# sch1.net
KiCad netlist of a schematic drawn in EAGLE
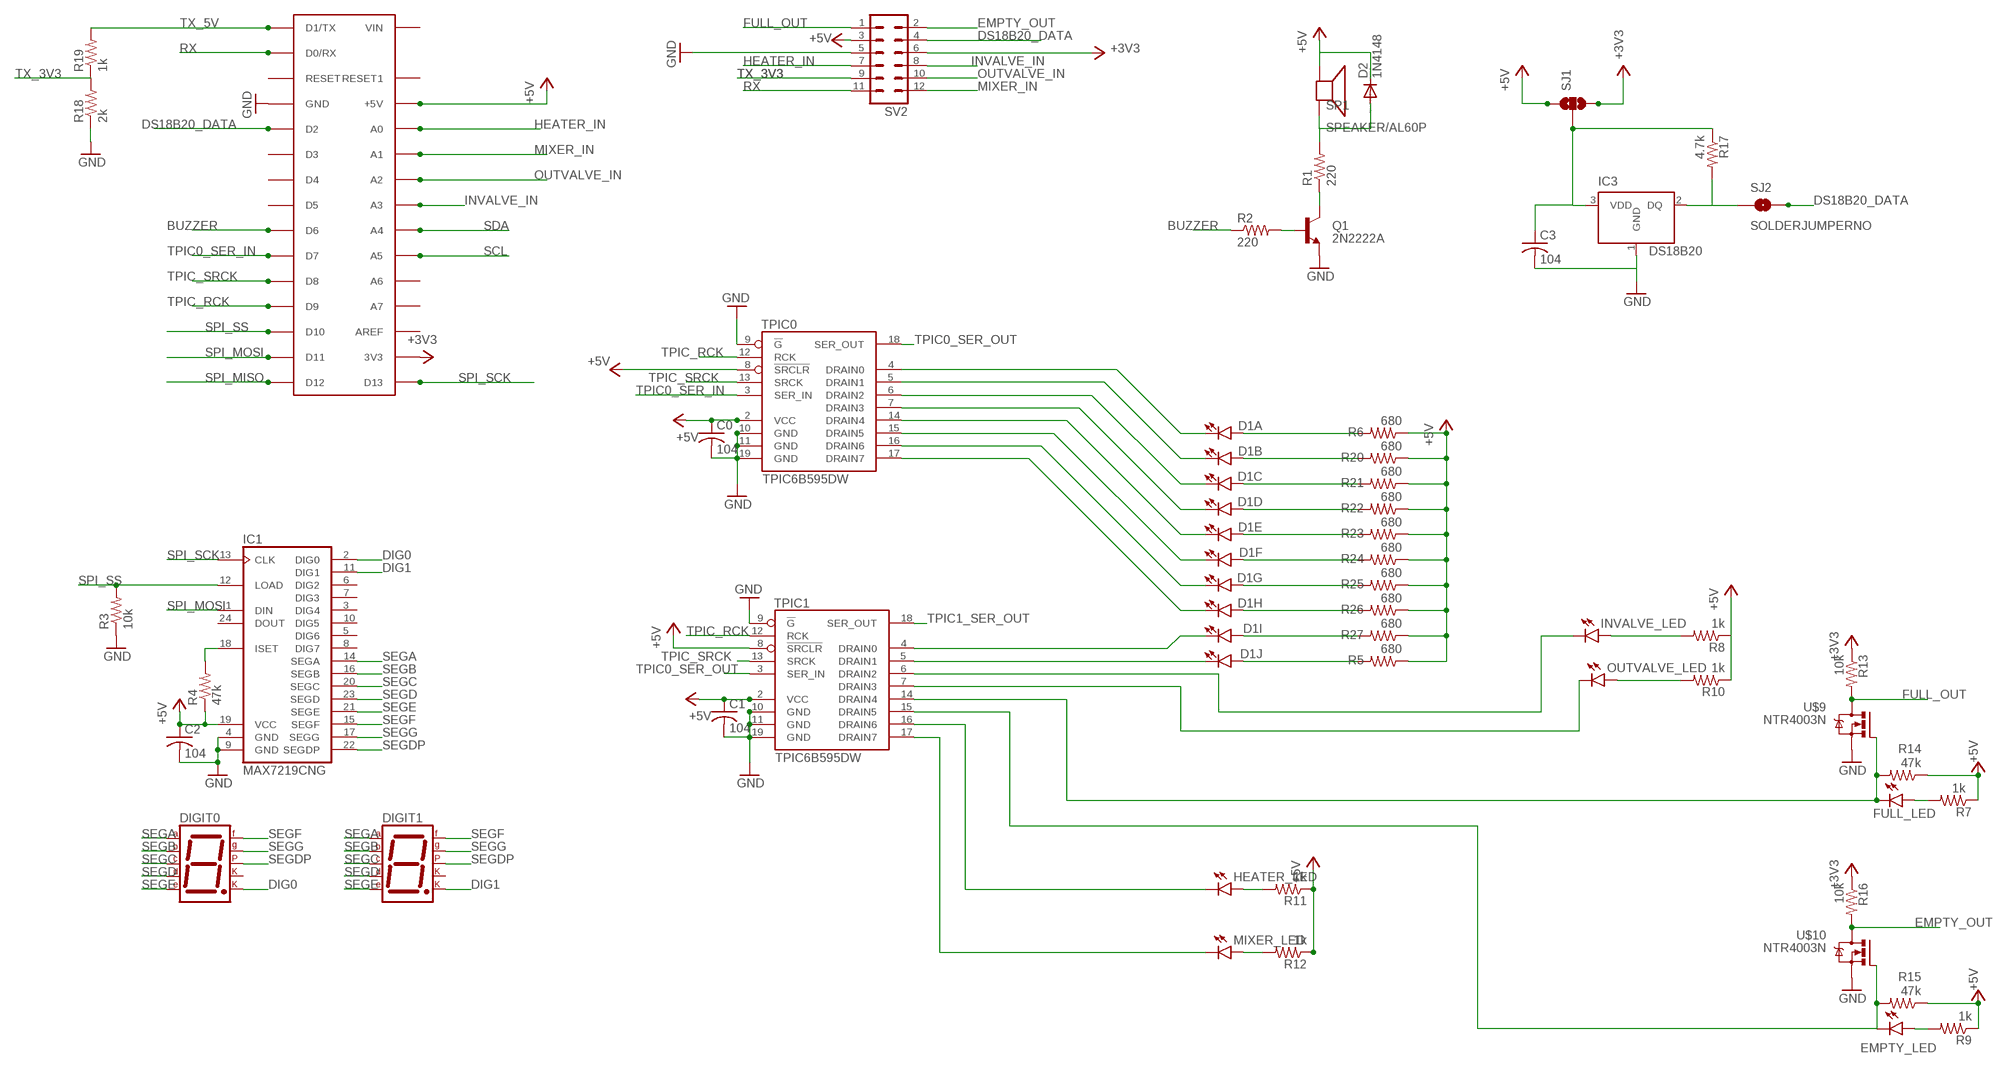
[diagram p0: schematic, sheet 1]

(export (version "E")
  (design (tool "Eeschema 10.0.6"))
  (components
    (comp (ref "ARDUINO")
      (value "ARDUINONANO")
      (footprint "eagle-import:PDIP-32")
      (libsource (lib "eagle-import") (part "ARDUINONANO"))
    )
    (comp (ref "C0")
      (value "104")
      (footprint "eagle-import:C0603")
      (libsource (lib "eagle-import") (part "C-USC0603"))
    )
    (comp (ref "C1")
      (value "104")
      (footprint "eagle-import:C0603")
      (libsource (lib "eagle-import") (part "C-USC0603"))
    )
    (comp (ref "C2")
      (value "104")
      (footprint "eagle-import:C0603")
      (libsource (lib "eagle-import") (part "C-USC0603"))
    )
    (comp (ref "C3")
      (value "104")
      (footprint "eagle-import:C0603")
      (libsource (lib "eagle-import") (part "C-USC0603"))
    )
    (comp (ref "D1")
      (value "LED_BARGRAPH_10")
      (footprint "eagle-import:LED_BARGAPH_10")
      (libsource (lib "eagle-import") (part "LED_BARGRAPH_10"))
    )
    (comp (ref "D2")
      (value "1N4148")
      (footprint "eagle-import:DO35-7")
      (libsource (lib "eagle-import") (part "1N4148DO35-7"))
    )
    (comp (ref "DIGIT0")
      (value "7SEG-CK")
      (footprint "eagle-import:7SEG-13")
      (libsource (lib "eagle-import") (part "7SEG-CK"))
    )
    (comp (ref "DIGIT1")
      (value "7SEG-CK")
      (footprint "eagle-import:7SEG-13")
      (libsource (lib "eagle-import") (part "7SEG-CK"))
    )
    (comp (ref "EMPTY_LED")
      (value "LED0603")
      (footprint "eagle-import:LED-0603")
      (libsource (lib "eagle-import") (part "LED0603"))
    )
    (comp (ref "FULL_LED")
      (value "LED0603")
      (footprint "eagle-import:LED-0603")
      (libsource (lib "eagle-import") (part "LED0603"))
    )
    (comp (ref "HEATER_LED")
      (value "LED0603")
      (footprint "eagle-import:LED-0603")
      (libsource (lib "eagle-import") (part "LED0603"))
    )
    (comp (ref "IC1")
      (value "MAX7219CNG")
      (footprint "eagle-import:DIL24-3")
      (fields (field (name "MF") "MAXIM"))
      (libsource (lib "eagle-import") (part "MAX7219CNG"))
    )
    (comp (ref "IC3")
      (value "DS18B20")
      (footprint "eagle-import:TO-92")
      (libsource (lib "eagle-import") (part "DS18B20"))
    )
    (comp (ref "INVALVE_LED")
      (value "LED0603")
      (footprint "eagle-import:LED-0603")
      (libsource (lib "eagle-import") (part "LED0603"))
    )
    (comp (ref "MIXER_LED")
      (value "LED0603")
      (footprint "eagle-import:LED-0603")
      (libsource (lib "eagle-import") (part "LED0603"))
    )
    (comp (ref "OUTVALVE_LED")
      (value "LED0603")
      (footprint "eagle-import:LED-0603")
      (libsource (lib "eagle-import") (part "LED0603"))
    )
    (comp (ref "Q1")
      (value "2N2222A")
      (footprint "eagle-import:SOT23-3")
      (libsource (lib "eagle-import") (part "TRANSISTOR_NPNMMBT2222A"))
    )
    (comp (ref "R1")
      (value "220")
      (footprint "eagle-import:R0603")
      (libsource (lib "eagle-import") (part "R-US_R0603"))
    )
    (comp (ref "R2")
      (value "220")
      (footprint "eagle-import:R0603")
      (libsource (lib "eagle-import") (part "R-US_R0603"))
    )
    (comp (ref "R3")
      (value "10k")
      (footprint "eagle-import:R0603")
      (libsource (lib "eagle-import") (part "R-US_R0603"))
    )
    (comp (ref "R4")
      (value "47k")
      (footprint "eagle-import:R0603")
      (libsource (lib "eagle-import") (part "R-US_R0603"))
    )
    (comp (ref "R5")
      (value "680")
      (footprint "eagle-import:R0603")
      (libsource (lib "eagle-import") (part "R-US_R0603"))
    )
    (comp (ref "R6")
      (value "680")
      (footprint "eagle-import:R0603")
      (libsource (lib "eagle-import") (part "R-US_R0603"))
    )
    (comp (ref "R7")
      (value "1k")
      (footprint "eagle-import:R0603")
      (libsource (lib "eagle-import") (part "R-US_R0603"))
    )
    (comp (ref "R8")
      (value "1k")
      (footprint "eagle-import:R0603")
      (libsource (lib "eagle-import") (part "R-US_R0603"))
    )
    (comp (ref "R9")
      (value "1k")
      (footprint "eagle-import:R0603")
      (libsource (lib "eagle-import") (part "R-US_R0603"))
    )
    (comp (ref "R10")
      (value "1k")
      (footprint "eagle-import:R0603")
      (libsource (lib "eagle-import") (part "R-US_R0603"))
    )
    (comp (ref "R11")
      (value "1k")
      (footprint "eagle-import:R0603")
      (libsource (lib "eagle-import") (part "R-US_R0603"))
    )
    (comp (ref "R12")
      (value "1k")
      (footprint "eagle-import:R0603")
      (libsource (lib "eagle-import") (part "R-US_R0603"))
    )
    (comp (ref "R13")
      (value "10k")
      (footprint "eagle-import:R0603")
      (libsource (lib "eagle-import") (part "R-US_R0603"))
    )
    (comp (ref "R14")
      (value "47k")
      (footprint "eagle-import:R0603")
      (libsource (lib "eagle-import") (part "R-US_R0603"))
    )
    (comp (ref "R15")
      (value "47k")
      (footprint "eagle-import:R0603")
      (libsource (lib "eagle-import") (part "R-US_R0603"))
    )
    (comp (ref "R16")
      (value "10k")
      (footprint "eagle-import:R0603")
      (libsource (lib "eagle-import") (part "R-US_R0603"))
    )
    (comp (ref "R17")
      (value "4.7k")
      (footprint "eagle-import:R0603")
      (libsource (lib "eagle-import") (part "R-US_R0603"))
    )
    (comp (ref "R18")
      (value "2k")
      (footprint "eagle-import:R0603")
      (libsource (lib "eagle-import") (part "R-US_R0603"))
    )
    (comp (ref "R19")
      (value "1k")
      (footprint "eagle-import:R0603")
      (libsource (lib "eagle-import") (part "R-US_R0603"))
    )
    (comp (ref "R20")
      (value "680")
      (footprint "eagle-import:R0603")
      (libsource (lib "eagle-import") (part "R-US_R0603"))
    )
    (comp (ref "R21")
      (value "680")
      (footprint "eagle-import:R0603")
      (libsource (lib "eagle-import") (part "R-US_R0603"))
    )
    (comp (ref "R22")
      (value "680")
      (footprint "eagle-import:R0603")
      (libsource (lib "eagle-import") (part "R-US_R0603"))
    )
    (comp (ref "R23")
      (value "680")
      (footprint "eagle-import:R0603")
      (libsource (lib "eagle-import") (part "R-US_R0603"))
    )
    (comp (ref "R24")
      (value "680")
      (footprint "eagle-import:R0603")
      (libsource (lib "eagle-import") (part "R-US_R0603"))
    )
    (comp (ref "R25")
      (value "680")
      (footprint "eagle-import:R0603")
      (libsource (lib "eagle-import") (part "R-US_R0603"))
    )
    (comp (ref "R26")
      (value "680")
      (footprint "eagle-import:R0603")
      (libsource (lib "eagle-import") (part "R-US_R0603"))
    )
    (comp (ref "R27")
      (value "680")
      (footprint "eagle-import:R0603")
      (libsource (lib "eagle-import") (part "R-US_R0603"))
    )
    (comp (ref "SJ1")
      (value "SOLDERJUMPER_2WAYS")
      (footprint "eagle-import:SJ_3")
      (libsource (lib "eagle-import") (part "SOLDERJUMPER_2WAYS"))
    )
    (comp (ref "SJ2")
      (value "SOLDERJUMPERNO")
      (footprint "eagle-import:SJ_2S-NO")
      (libsource (lib "eagle-import") (part "SOLDERJUMPERNO"))
    )
    (comp (ref "SP1")
      (value "SPEAKER/AL60P")
      (footprint "eagle-import:AL60P")
      (libsource (lib "eagle-import") (part "SPEAKER/AL60P"))
    )
    (comp (ref "SV2")
      (value "MA06-2")
      (footprint "eagle-import:MA06-2")
      (libsource (lib "eagle-import") (part "MA06-2"))
    )
    (comp (ref "TPIC0")
      (value "TPIC6B595DW")
      (footprint "eagle-import:SO20W")
      (libsource (lib "eagle-import") (part "TPIC6B595DW"))
    )
    (comp (ref "TPIC1")
      (value "TPIC6B595DW")
      (footprint "eagle-import:SO20W")
      (libsource (lib "eagle-import") (part "TPIC6B595DW"))
    )
    (comp (ref "U$9")
      (value "NTR4003N")
      (footprint "eagle-import:SOT23")
      (libsource (lib "eagle-import") (part "NTR4003N"))
    )
    (comp (ref "U$10")
      (value "NTR4003N")
      (footprint "eagle-import:SOT23")
      (libsource (lib "eagle-import") (part "NTR4003N"))
    )
  )
  (nets
    (net (code "1") (name "+3V3") (class "Default")
      (node (ref "ARDUINO") (pin "17") (pinfunction "3V3_17") (pintype "bidirectional"))
      (node (ref "R13") (pin "1") (pinfunction "1_1") (pintype "passive"))
      (node (ref "R16") (pin "1") (pinfunction "1_1") (pintype "passive"))
      (node (ref "SJ1") (pin "3") (pinfunction "3_3") (pintype "passive"))
      (node (ref "SV2") (pin "6") (pinfunction "6_6") (pintype "passive"))
    )
    (net (code "2") (name "+5V") (class "Default")
      (node (ref "ARDUINO") (pin "27") (pinfunction "+5V_27") (pintype "bidirectional"))
      (node (ref "C0") (pin "1") (pinfunction "1_1") (pintype "passive"))
      (node (ref "C1") (pin "1") (pinfunction "1_1") (pintype "passive"))
      (node (ref "C2") (pin "1") (pinfunction "1_1") (pintype "passive"))
      (node (ref "D2") (pin "C") (pinfunction "C_C") (pintype "passive"))
      (node (ref "IC1") (pin "19") (pinfunction "VCC_19") (pintype "power_in"))
      (node (ref "R10") (pin "1") (pinfunction "1_1") (pintype "passive"))
      (node (ref "R11") (pin "1") (pinfunction "1_1") (pintype "passive"))
      (node (ref "R12") (pin "1") (pinfunction "1_1") (pintype "passive"))
      (node (ref "R14") (pin "1") (pinfunction "1_1") (pintype "passive"))
      (node (ref "R15") (pin "1") (pinfunction "1_1") (pintype "passive"))
      (node (ref "R20") (pin "1") (pinfunction "1_1") (pintype "passive"))
      (node (ref "R21") (pin "1") (pinfunction "1_1") (pintype "passive"))
      (node (ref "R22") (pin "1") (pinfunction "1_1") (pintype "passive"))
      (node (ref "R23") (pin "1") (pinfunction "1_1") (pintype "passive"))
      (node (ref "R24") (pin "1") (pinfunction "1_1") (pintype "passive"))
      (node (ref "R25") (pin "1") (pinfunction "1_1") (pintype "passive"))
      (node (ref "R26") (pin "1") (pinfunction "1_1") (pintype "passive"))
      (node (ref "R27") (pin "1") (pinfunction "1_1") (pintype "passive"))
      (node (ref "R4") (pin "1") (pinfunction "1_1") (pintype "passive"))
      (node (ref "R5") (pin "1") (pinfunction "1_1") (pintype "passive"))
      (node (ref "R6") (pin "1") (pinfunction "1_1") (pintype "passive"))
      (node (ref "R7") (pin "1") (pinfunction "1_1") (pintype "passive"))
      (node (ref "R8") (pin "1") (pinfunction "1_1") (pintype "passive"))
      (node (ref "R9") (pin "1") (pinfunction "1_1") (pintype "passive"))
      (node (ref "SJ1") (pin "1") (pinfunction "1_1") (pintype "passive"))
      (node (ref "SP1") (pin "1") (pinfunction "+_1") (pintype "passive"))
      (node (ref "SV2") (pin "3") (pinfunction "3_3") (pintype "passive"))
      (node (ref "TPIC0") (pin "2") (pinfunction "VCC_2") (pintype "power_in"))
      (node (ref "TPIC0") (pin "8") (pinfunction "~{SRCLR}_8") (pintype "input"))
      (node (ref "TPIC1") (pin "2") (pinfunction "VCC_2") (pintype "power_in"))
      (node (ref "TPIC1") (pin "8") (pinfunction "~{SRCLR}_8") (pintype "input"))
    )
    (net (code "3") (name "/BUZZER") (class "Default")
      (node (ref "ARDUINO") (pin "9") (pinfunction "D6_9") (pintype "bidirectional"))
      (node (ref "R2") (pin "1") (pinfunction "1_1") (pintype "passive"))
    )
    (net (code "4") (name "/DIG0") (class "Default")
      (node (ref "DIGIT0") (pin "8") (pinfunction "CK2_8") (pintype "passive"))
      (node (ref "IC1") (pin "2") (pinfunction "DIG0_2") (pintype "output"))
    )
    (net (code "5") (name "/DIG1") (class "Default")
      (node (ref "DIGIT1") (pin "8") (pinfunction "CK2_8") (pintype "passive"))
      (node (ref "IC1") (pin "11") (pinfunction "DIG1_11") (pintype "output"))
    )
    (net (code "6") (name "/DS18B20_DATA") (class "Default")
      (node (ref "ARDUINO") (pin "5") (pinfunction "D2_5") (pintype "bidirectional"))
      (node (ref "SJ2") (pin "2") (pinfunction "2_2") (pintype "passive"))
      (node (ref "SV2") (pin "4") (pinfunction "4_4") (pintype "passive"))
    )
    (net (code "7") (name "/EMPTY_OUT") (class "Default")
      (node (ref "R16") (pin "2") (pinfunction "2_2") (pintype "passive"))
      (node (ref "SV2") (pin "2") (pinfunction "2_2") (pintype "passive"))
      (node (ref "U$10") (pin "3") (pinfunction "D_3") (pintype "passive"))
    )
    (net (code "8") (name "/FULL_OUT") (class "Default")
      (node (ref "R13") (pin "2") (pinfunction "2_2") (pintype "passive"))
      (node (ref "SV2") (pin "1") (pinfunction "1_1") (pintype "passive"))
      (node (ref "U$9") (pin "3") (pinfunction "D_3") (pintype "passive"))
    )
    (net (code "9") (name "/HEATER_IN") (class "Default")
      (node (ref "ARDUINO") (pin "19") (pinfunction "A0_19") (pintype "bidirectional"))
      (node (ref "SV2") (pin "7") (pinfunction "7_7") (pintype "passive"))
    )
    (net (code "10") (name "/INVALVE_IN") (class "Default")
      (node (ref "ARDUINO") (pin "22") (pinfunction "A3_22") (pintype "bidirectional"))
      (node (ref "SV2") (pin "8") (pinfunction "8_8") (pintype "passive"))
    )
    (net (code "11") (name "/MIXER_IN") (class "Default")
      (node (ref "ARDUINO") (pin "20") (pinfunction "A1_20") (pintype "bidirectional"))
      (node (ref "SV2") (pin "12") (pinfunction "12_12") (pintype "passive"))
    )
    (net (code "12") (name "/OUTVALVE_IN") (class "Default")
      (node (ref "ARDUINO") (pin "21") (pinfunction "A2_21") (pintype "bidirectional"))
      (node (ref "SV2") (pin "10") (pinfunction "10_10") (pintype "passive"))
    )
    (net (code "13") (name "/RX") (class "Default")
      (node (ref "ARDUINO") (pin "2") (pinfunction "D0/RX_2") (pintype "bidirectional"))
      (node (ref "SV2") (pin "11") (pinfunction "11_11") (pintype "passive"))
    )
    (net (code "14") (name "/SCL") (class "Default")
      (node (ref "ARDUINO") (pin "24") (pinfunction "A5_24") (pintype "bidirectional"))
    )
    (net (code "15") (name "/SDA") (class "Default")
      (node (ref "ARDUINO") (pin "23") (pinfunction "A4_23") (pintype "bidirectional"))
    )
    (net (code "16") (name "/SEGA") (class "Default")
      (node (ref "DIGIT0") (pin "7") (pinfunction "A_7") (pintype "passive"))
      (node (ref "DIGIT1") (pin "7") (pinfunction "A_7") (pintype "passive"))
      (node (ref "IC1") (pin "14") (pinfunction "SEGA_14") (pintype "output"))
    )
    (net (code "17") (name "/SEGB") (class "Default")
      (node (ref "DIGIT0") (pin "6") (pinfunction "B_6") (pintype "passive"))
      (node (ref "DIGIT1") (pin "6") (pinfunction "B_6") (pintype "passive"))
      (node (ref "IC1") (pin "16") (pinfunction "SEGB_16") (pintype "output"))
    )
    (net (code "18") (name "/SEGC") (class "Default")
      (node (ref "DIGIT0") (pin "4") (pinfunction "C_4") (pintype "passive"))
      (node (ref "DIGIT1") (pin "4") (pinfunction "C_4") (pintype "passive"))
      (node (ref "IC1") (pin "20") (pinfunction "SEGC_20") (pintype "output"))
    )
    (net (code "19") (name "/SEGD") (class "Default")
      (node (ref "DIGIT0") (pin "2") (pinfunction "D_2") (pintype "passive"))
      (node (ref "DIGIT1") (pin "2") (pinfunction "D_2") (pintype "passive"))
      (node (ref "IC1") (pin "23") (pinfunction "SEGD_23") (pintype "output"))
    )
    (net (code "20") (name "/SEGDP") (class "Default")
      (node (ref "DIGIT0") (pin "5") (pinfunction "DP_5") (pintype "passive"))
      (node (ref "DIGIT1") (pin "5") (pinfunction "DP_5") (pintype "passive"))
      (node (ref "IC1") (pin "22") (pinfunction "SEGDP_22") (pintype "output"))
    )
    (net (code "21") (name "/SEGE") (class "Default")
      (node (ref "DIGIT0") (pin "1") (pinfunction "E_1") (pintype "passive"))
      (node (ref "DIGIT1") (pin "1") (pinfunction "E_1") (pintype "passive"))
      (node (ref "IC1") (pin "21") (pinfunction "SEGE_21") (pintype "output"))
    )
    (net (code "22") (name "/SEGF") (class "Default")
      (node (ref "DIGIT0") (pin "9") (pinfunction "F_9") (pintype "passive"))
      (node (ref "DIGIT1") (pin "9") (pinfunction "F_9") (pintype "passive"))
      (node (ref "IC1") (pin "15") (pinfunction "SEGF_15") (pintype "output"))
    )
    (net (code "23") (name "/SEGG") (class "Default")
      (node (ref "DIGIT0") (pin "10") (pinfunction "G_10") (pintype "passive"))
      (node (ref "DIGIT1") (pin "10") (pinfunction "G_10") (pintype "passive"))
      (node (ref "IC1") (pin "17") (pinfunction "SEGG_17") (pintype "output"))
    )
    (net (code "24") (name "/SPI_MISO") (class "Default")
      (node (ref "ARDUINO") (pin "15") (pinfunction "D12_15") (pintype "bidirectional"))
    )
    (net (code "25") (name "/SPI_MOSI") (class "Default")
      (node (ref "ARDUINO") (pin "14") (pinfunction "D11_14") (pintype "bidirectional"))
      (node (ref "IC1") (pin "1") (pinfunction "DIN_1") (pintype "input"))
    )
    (net (code "26") (name "/SPI_SCK") (class "Default")
      (node (ref "ARDUINO") (pin "16") (pinfunction "D13_16") (pintype "bidirectional"))
      (node (ref "IC1") (pin "13") (pinfunction "CLK_13") (pintype "input"))
    )
    (net (code "27") (name "/SPI_SS") (class "Default")
      (node (ref "ARDUINO") (pin "13") (pinfunction "D10_13") (pintype "bidirectional"))
      (node (ref "IC1") (pin "12") (pinfunction "LOAD_12") (pintype "input"))
      (node (ref "R3") (pin "2") (pinfunction "2_2") (pintype "passive"))
    )
    (net (code "28") (name "/TPIC0_SER_IN") (class "Default")
      (node (ref "ARDUINO") (pin "10") (pinfunction "D7_10") (pintype "bidirectional"))
      (node (ref "TPIC0") (pin "3") (pinfunction "SER_IN_3") (pintype "input"))
    )
    (net (code "29") (name "/TPIC0_SER_OUT") (class "Default")
      (node (ref "TPIC0") (pin "18") (pinfunction "SER_OUT_18") (pintype "output"))
      (node (ref "TPIC1") (pin "3") (pinfunction "SER_IN_3") (pintype "input"))
    )
    (net (code "30") (name "/TPIC1_SER_OUT") (class "Default")
      (node (ref "TPIC1") (pin "18") (pinfunction "SER_OUT_18") (pintype "output"))
    )
    (net (code "31") (name "/TPIC_RCK") (class "Default")
      (node (ref "ARDUINO") (pin "12") (pinfunction "D9_12") (pintype "bidirectional"))
      (node (ref "TPIC0") (pin "12") (pinfunction "RCK_12") (pintype "input"))
      (node (ref "TPIC1") (pin "12") (pinfunction "RCK_12") (pintype "input"))
    )
    (net (code "32") (name "/TPIC_SRCK") (class "Default")
      (node (ref "ARDUINO") (pin "11") (pinfunction "D8_11") (pintype "bidirectional"))
      (node (ref "TPIC0") (pin "13") (pinfunction "SRCK_13") (pintype "input"))
      (node (ref "TPIC1") (pin "13") (pinfunction "SRCK_13") (pintype "input"))
    )
    (net (code "33") (name "/TX_3V3") (class "Default")
      (node (ref "R18") (pin "2") (pinfunction "2_2") (pintype "passive"))
      (node (ref "R19") (pin "1") (pinfunction "1_1") (pintype "passive"))
      (node (ref "SV2") (pin "9") (pinfunction "9_9") (pintype "passive"))
    )
    (net (code "34") (name "/TX_5V") (class "Default")
      (node (ref "ARDUINO") (pin "1") (pinfunction "D1/TX_1") (pintype "bidirectional"))
      (node (ref "R19") (pin "2") (pinfunction "2_2") (pintype "passive"))
    )
    (net (code "35") (name "GND") (class "Default")
      (node (ref "ARDUINO") (pin "29") (pinfunction "GND_29") (pintype "bidirectional"))
      (node (ref "ARDUINO") (pin "4") (pinfunction "GND_4") (pintype "bidirectional"))
      (node (ref "C0") (pin "2") (pinfunction "2_2") (pintype "passive"))
      (node (ref "C1") (pin "2") (pinfunction "2_2") (pintype "passive"))
      (node (ref "C2") (pin "2") (pinfunction "2_2") (pintype "passive"))
      (node (ref "C3") (pin "2") (pinfunction "2_2") (pintype "passive"))
      (node (ref "IC1") (pin "4") (pinfunction "GND_4") (pintype "power_in"))
      (node (ref "IC1") (pin "9") (pinfunction "GND_9") (pintype "power_in"))
      (node (ref "IC3") (pin "1") (pinfunction "GND_1") (pintype "power_in"))
      (node (ref "Q1") (pin "2") (pinfunction "E_2") (pintype "passive"))
      (node (ref "R18") (pin "1") (pinfunction "1_1") (pintype "passive"))
      (node (ref "R3") (pin "1") (pinfunction "1_1") (pintype "passive"))
      (node (ref "SV2") (pin "5") (pinfunction "5_5") (pintype "passive"))
      (node (ref "TPIC0") (pin "10") (pinfunction "GND_10") (pintype "power_in"))
      (node (ref "TPIC0") (pin "11") (pinfunction "GND_11") (pintype "power_in"))
      (node (ref "TPIC0") (pin "19") (pinfunction "GND_19") (pintype "power_in"))
      (node (ref "TPIC0") (pin "9") (pinfunction "~{G}_9") (pintype "input"))
      (node (ref "TPIC1") (pin "10") (pinfunction "GND_10") (pintype "power_in"))
      (node (ref "TPIC1") (pin "11") (pinfunction "GND_11") (pintype "power_in"))
      (node (ref "TPIC1") (pin "19") (pinfunction "GND_19") (pintype "power_in"))
      (node (ref "TPIC1") (pin "9") (pinfunction "~{G}_9") (pintype "input"))
      (node (ref "U$10") (pin "2") (pinfunction "S_2") (pintype "passive"))
      (node (ref "U$9") (pin "2") (pinfunction "S_2") (pintype "passive"))
    )
    (net (code "36") (name "Net-(D1A-A)") (class "Default")
      (node (ref "D1") (pin "1") (pinfunction "A_1") (pintype "passive"))
      (node (ref "R6") (pin "2") (pinfunction "2_2") (pintype "passive"))
    )
    (net (code "37") (name "Net-(D1A-C)") (class "Default")
      (node (ref "D1") (pin "20") (pinfunction "C_20") (pintype "passive"))
      (node (ref "TPIC0") (pin "4") (pinfunction "DRAIN0_4") (pintype "open_collector"))
    )
    (net (code "38") (name "Net-(D1B-A)") (class "Default")
      (node (ref "D1") (pin "2") (pinfunction "A_2") (pintype "passive"))
      (node (ref "R20") (pin "2") (pinfunction "2_2") (pintype "passive"))
    )
    (net (code "39") (name "Net-(D1B-C)") (class "Default")
      (node (ref "D1") (pin "19") (pinfunction "C_19") (pintype "passive"))
      (node (ref "TPIC0") (pin "5") (pinfunction "DRAIN1_5") (pintype "open_collector"))
    )
    (net (code "40") (name "Net-(D1C-A)") (class "Default")
      (node (ref "D1") (pin "3") (pinfunction "A_3") (pintype "passive"))
      (node (ref "R21") (pin "2") (pinfunction "2_2") (pintype "passive"))
    )
    (net (code "41") (name "Net-(D1C-C)") (class "Default")
      (node (ref "D1") (pin "18") (pinfunction "C_18") (pintype "passive"))
      (node (ref "TPIC0") (pin "6") (pinfunction "DRAIN2_6") (pintype "open_collector"))
    )
    (net (code "42") (name "Net-(D1D-A)") (class "Default")
      (node (ref "D1") (pin "4") (pinfunction "A_4") (pintype "passive"))
      (node (ref "R22") (pin "2") (pinfunction "2_2") (pintype "passive"))
    )
    (net (code "43") (name "Net-(D1D-C)") (class "Default")
      (node (ref "D1") (pin "17") (pinfunction "C_17") (pintype "passive"))
      (node (ref "TPIC0") (pin "7") (pinfunction "DRAIN3_7") (pintype "open_collector"))
    )
    (net (code "44") (name "Net-(D1E-A)") (class "Default")
      (node (ref "D1") (pin "5") (pinfunction "A_5") (pintype "passive"))
      (node (ref "R23") (pin "2") (pinfunction "2_2") (pintype "passive"))
    )
    (net (code "45") (name "Net-(D1E-C)") (class "Default")
      (node (ref "D1") (pin "16") (pinfunction "C_16") (pintype "passive"))
      (node (ref "TPIC0") (pin "14") (pinfunction "DRAIN4_14") (pintype "open_collector"))
    )
    (net (code "46") (name "Net-(D1F-A)") (class "Default")
      (node (ref "D1") (pin "6") (pinfunction "A_6") (pintype "passive"))
      (node (ref "R24") (pin "2") (pinfunction "2_2") (pintype "passive"))
    )
    (net (code "47") (name "Net-(D1F-C)") (class "Default")
      (node (ref "D1") (pin "15") (pinfunction "C_15") (pintype "passive"))
      (node (ref "TPIC0") (pin "15") (pinfunction "DRAIN5_15") (pintype "open_collector"))
    )
    (net (code "48") (name "Net-(D1G-A)") (class "Default")
      (node (ref "D1") (pin "7") (pinfunction "A_7") (pintype "passive"))
      (node (ref "R25") (pin "2") (pinfunction "2_2") (pintype "passive"))
    )
    (net (code "49") (name "Net-(D1G-C)") (class "Default")
      (node (ref "D1") (pin "14") (pinfunction "C_14") (pintype "passive"))
      (node (ref "TPIC0") (pin "16") (pinfunction "DRAIN6_16") (pintype "open_collector"))
    )
    (net (code "50") (name "Net-(D1H-A)") (class "Default")
      (node (ref "D1") (pin "8") (pinfunction "A_8") (pintype "passive"))
      (node (ref "R26") (pin "2") (pinfunction "2_2") (pintype "passive"))
    )
    (net (code "51") (name "Net-(D1H-C)") (class "Default")
      (node (ref "D1") (pin "13") (pinfunction "C_13") (pintype "passive"))
      (node (ref "TPIC0") (pin "17") (pinfunction "DRAIN7_17") (pintype "open_collector"))
    )
    (net (code "52") (name "Net-(D1I-A)") (class "Default")
      (node (ref "D1") (pin "9") (pinfunction "A_9") (pintype "passive"))
      (node (ref "R27") (pin "2") (pinfunction "2_2") (pintype "passive"))
    )
    (net (code "53") (name "Net-(D1I-C)") (class "Default")
      (node (ref "D1") (pin "12") (pinfunction "C_12") (pintype "passive"))
      (node (ref "TPIC1") (pin "4") (pinfunction "DRAIN0_4") (pintype "open_collector"))
    )
    (net (code "54") (name "Net-(D1J-A)") (class "Default")
      (node (ref "D1") (pin "10") (pinfunction "A_10") (pintype "passive"))
      (node (ref "R5") (pin "2") (pinfunction "2_2") (pintype "passive"))
    )
    (net (code "55") (name "Net-(D1J-C)") (class "Default")
      (node (ref "D1") (pin "11") (pinfunction "C_11") (pintype "passive"))
      (node (ref "TPIC1") (pin "5") (pinfunction "DRAIN1_5") (pintype "open_collector"))
    )
    (net (code "56") (name "Net-(EMPTY_LED-PadA)") (class "Default")
      (node (ref "EMPTY_LED") (pin "A") (pinfunction "A_A") (pintype "passive"))
      (node (ref "R9") (pin "2") (pinfunction "2_2") (pintype "passive"))
    )
    (net (code "57") (name "Net-(FULL_LED-PadA)") (class "Default")
      (node (ref "FULL_LED") (pin "A") (pinfunction "A_A") (pintype "passive"))
      (node (ref "R7") (pin "2") (pinfunction "2_2") (pintype "passive"))
    )
    (net (code "58") (name "Net-(HEATER_LED-PadA)") (class "Default")
      (node (ref "HEATER_LED") (pin "A") (pinfunction "A_A") (pintype "passive"))
      (node (ref "R11") (pin "2") (pinfunction "2_2") (pintype "passive"))
    )
    (net (code "59") (name "Net-(IC1-ISET)") (class "Default")
      (node (ref "IC1") (pin "18") (pinfunction "ISET_18") (pintype "input"))
      (node (ref "R4") (pin "2") (pinfunction "2_2") (pintype "passive"))
    )
    (net (code "60") (name "Net-(IC3-DQ)") (class "Default")
      (node (ref "IC3") (pin "2") (pinfunction "DQ_2") (pintype "output"))
      (node (ref "R17") (pin "2") (pinfunction "2_2") (pintype "passive"))
      (node (ref "SJ2") (pin "1") (pinfunction "1_1") (pintype "passive"))
    )
    (net (code "61") (name "Net-(IC3-VDD)") (class "Default")
      (node (ref "C3") (pin "1") (pinfunction "1_1") (pintype "passive"))
      (node (ref "IC3") (pin "3") (pinfunction "VDD_3") (pintype "input"))
      (node (ref "R17") (pin "1") (pinfunction "1_1") (pintype "passive"))
      (node (ref "SJ1") (pin "2") (pinfunction "2_2") (pintype "passive"))
    )
    (net (code "62") (name "Net-(INVALVE_LED-PadA)") (class "Default")
      (node (ref "INVALVE_LED") (pin "A") (pinfunction "A_A") (pintype "passive"))
      (node (ref "R8") (pin "2") (pinfunction "2_2") (pintype "passive"))
    )
    (net (code "63") (name "Net-(MIXER_LED-PadA)") (class "Default")
      (node (ref "MIXER_LED") (pin "A") (pinfunction "A_A") (pintype "passive"))
      (node (ref "R12") (pin "2") (pinfunction "2_2") (pintype "passive"))
    )
    (net (code "64") (name "Net-(OUTVALVE_LED-PadA)") (class "Default")
      (node (ref "OUTVALVE_LED") (pin "A") (pinfunction "A_A") (pintype "passive"))
      (node (ref "R10") (pin "2") (pinfunction "2_2") (pintype "passive"))
    )
    (net (code "65") (name "Net-(Q1-B)") (class "Default")
      (node (ref "Q1") (pin "1") (pinfunction "B_1") (pintype "passive"))
      (node (ref "R2") (pin "2") (pinfunction "2_2") (pintype "passive"))
    )
    (net (code "66") (name "Net-(Q1-C)") (class "Default")
      (node (ref "Q1") (pin "3") (pinfunction "C_3") (pintype "passive"))
      (node (ref "R1") (pin "1") (pinfunction "1_1") (pintype "passive"))
    )
    (net (code "67") (name "Net-(SP1--)") (class "Default")
      (node (ref "D2") (pin "A") (pinfunction "A_A") (pintype "passive"))
      (node (ref "R1") (pin "2") (pinfunction "2_2") (pintype "passive"))
      (node (ref "SP1") (pin "2") (pinfunction "-_2") (pintype "passive"))
    )
    (net (code "68") (name "Net-(TPIC1-DRAIN2)") (class "Default")
      (node (ref "INVALVE_LED") (pin "C") (pinfunction "C_C") (pintype "passive"))
      (node (ref "TPIC1") (pin "6") (pinfunction "DRAIN2_6") (pintype "open_collector"))
    )
    (net (code "69") (name "Net-(TPIC1-DRAIN3)") (class "Default")
      (node (ref "OUTVALVE_LED") (pin "C") (pinfunction "C_C") (pintype "passive"))
      (node (ref "TPIC1") (pin "7") (pinfunction "DRAIN3_7") (pintype "open_collector"))
    )
    (net (code "70") (name "Net-(TPIC1-DRAIN4)") (class "Default")
      (node (ref "FULL_LED") (pin "C") (pinfunction "C_C") (pintype "passive"))
      (node (ref "R14") (pin "2") (pinfunction "2_2") (pintype "passive"))
      (node (ref "TPIC1") (pin "14") (pinfunction "DRAIN4_14") (pintype "open_collector"))
      (node (ref "U$9") (pin "1") (pinfunction "G_1") (pintype "passive"))
    )
    (net (code "71") (name "Net-(TPIC1-DRAIN5)") (class "Default")
      (node (ref "EMPTY_LED") (pin "C") (pinfunction "C_C") (pintype "passive"))
      (node (ref "R15") (pin "2") (pinfunction "2_2") (pintype "passive"))
      (node (ref "TPIC1") (pin "15") (pinfunction "DRAIN5_15") (pintype "open_collector"))
      (node (ref "U$10") (pin "1") (pinfunction "G_1") (pintype "passive"))
    )
    (net (code "72") (name "Net-(TPIC1-DRAIN6)") (class "Default")
      (node (ref "HEATER_LED") (pin "C") (pinfunction "C_C") (pintype "passive"))
      (node (ref "TPIC1") (pin "16") (pinfunction "DRAIN6_16") (pintype "open_collector"))
    )
    (net (code "73") (name "Net-(TPIC1-DRAIN7)") (class "Default")
      (node (ref "MIXER_LED") (pin "C") (pinfunction "C_C") (pintype "passive"))
      (node (ref "TPIC1") (pin "17") (pinfunction "DRAIN7_17") (pintype "open_collector"))
    )
    (net (code "74") (name "unconnected-(ARDUINO-A6-Pad25)") (class "Default")
      (node (ref "ARDUINO") (pin "25") (pinfunction "A6_25") (pintype "bidirectional"))
    )
    (net (code "75") (name "unconnected-(ARDUINO-A7-Pad26)") (class "Default")
      (node (ref "ARDUINO") (pin "26") (pinfunction "A7_26") (pintype "bidirectional"))
    )
    (net (code "76") (name "unconnected-(ARDUINO-AREF-Pad18)") (class "Default")
      (node (ref "ARDUINO") (pin "18") (pinfunction "AREF_18") (pintype "bidirectional"))
    )
    (net (code "77") (name "unconnected-(ARDUINO-D3-Pad6)") (class "Default")
      (node (ref "ARDUINO") (pin "6") (pinfunction "D3_6") (pintype "bidirectional"))
    )
    (net (code "78") (name "unconnected-(ARDUINO-D4-Pad7)") (class "Default")
      (node (ref "ARDUINO") (pin "7") (pinfunction "D4_7") (pintype "bidirectional"))
    )
    (net (code "79") (name "unconnected-(ARDUINO-D5-Pad8)") (class "Default")
      (node (ref "ARDUINO") (pin "8") (pinfunction "D5_8") (pintype "bidirectional"))
    )
    (net (code "80") (name "unconnected-(ARDUINO-RESET-Pad3)") (class "Default")
      (node (ref "ARDUINO") (pin "3") (pinfunction "RESET_3") (pintype "bidirectional"))
    )
    (net (code "81") (name "unconnected-(ARDUINO-RESET1-Pad28)") (class "Default")
      (node (ref "ARDUINO") (pin "28") (pinfunction "RESET1_28") (pintype "bidirectional"))
    )
    (net (code "82") (name "unconnected-(ARDUINO-VIN-Pad30)") (class "Default")
      (node (ref "ARDUINO") (pin "30") (pinfunction "VIN_30") (pintype "bidirectional"))
    )
    (net (code "83") (name "unconnected-(DIGIT0-CK1-Pad3)") (class "Default")
      (node (ref "DIGIT0") (pin "3") (pinfunction "CK1_3") (pintype "passive"))
    )
    (net (code "84") (name "unconnected-(DIGIT1-CK1-Pad3)") (class "Default")
      (node (ref "DIGIT1") (pin "3") (pinfunction "CK1_3") (pintype "passive"))
    )
    (net (code "85") (name "unconnected-(IC1-DIG2-Pad6)") (class "Default")
      (node (ref "IC1") (pin "6") (pinfunction "DIG2_6") (pintype "output"))
    )
    (net (code "86") (name "unconnected-(IC1-DIG3-Pad7)") (class "Default")
      (node (ref "IC1") (pin "7") (pinfunction "DIG3_7") (pintype "output"))
    )
    (net (code "87") (name "unconnected-(IC1-DIG4-Pad3)") (class "Default")
      (node (ref "IC1") (pin "3") (pinfunction "DIG4_3") (pintype "output"))
    )
    (net (code "88") (name "unconnected-(IC1-DIG5-Pad10)") (class "Default")
      (node (ref "IC1") (pin "10") (pinfunction "DIG5_10") (pintype "output"))
    )
    (net (code "89") (name "unconnected-(IC1-DIG6-Pad5)") (class "Default")
      (node (ref "IC1") (pin "5") (pinfunction "DIG6_5") (pintype "output"))
    )
    (net (code "90") (name "unconnected-(IC1-DIG7-Pad8)") (class "Default")
      (node (ref "IC1") (pin "8") (pinfunction "DIG7_8") (pintype "output"))
    )
    (net (code "91") (name "unconnected-(IC1-DOUT-Pad24)") (class "Default")
      (node (ref "IC1") (pin "24") (pinfunction "DOUT_24") (pintype "output"))
    )
  )
)
